# RC_CAR_Tx.net
KiCad netlist of a schematic drawn in EasyEDA
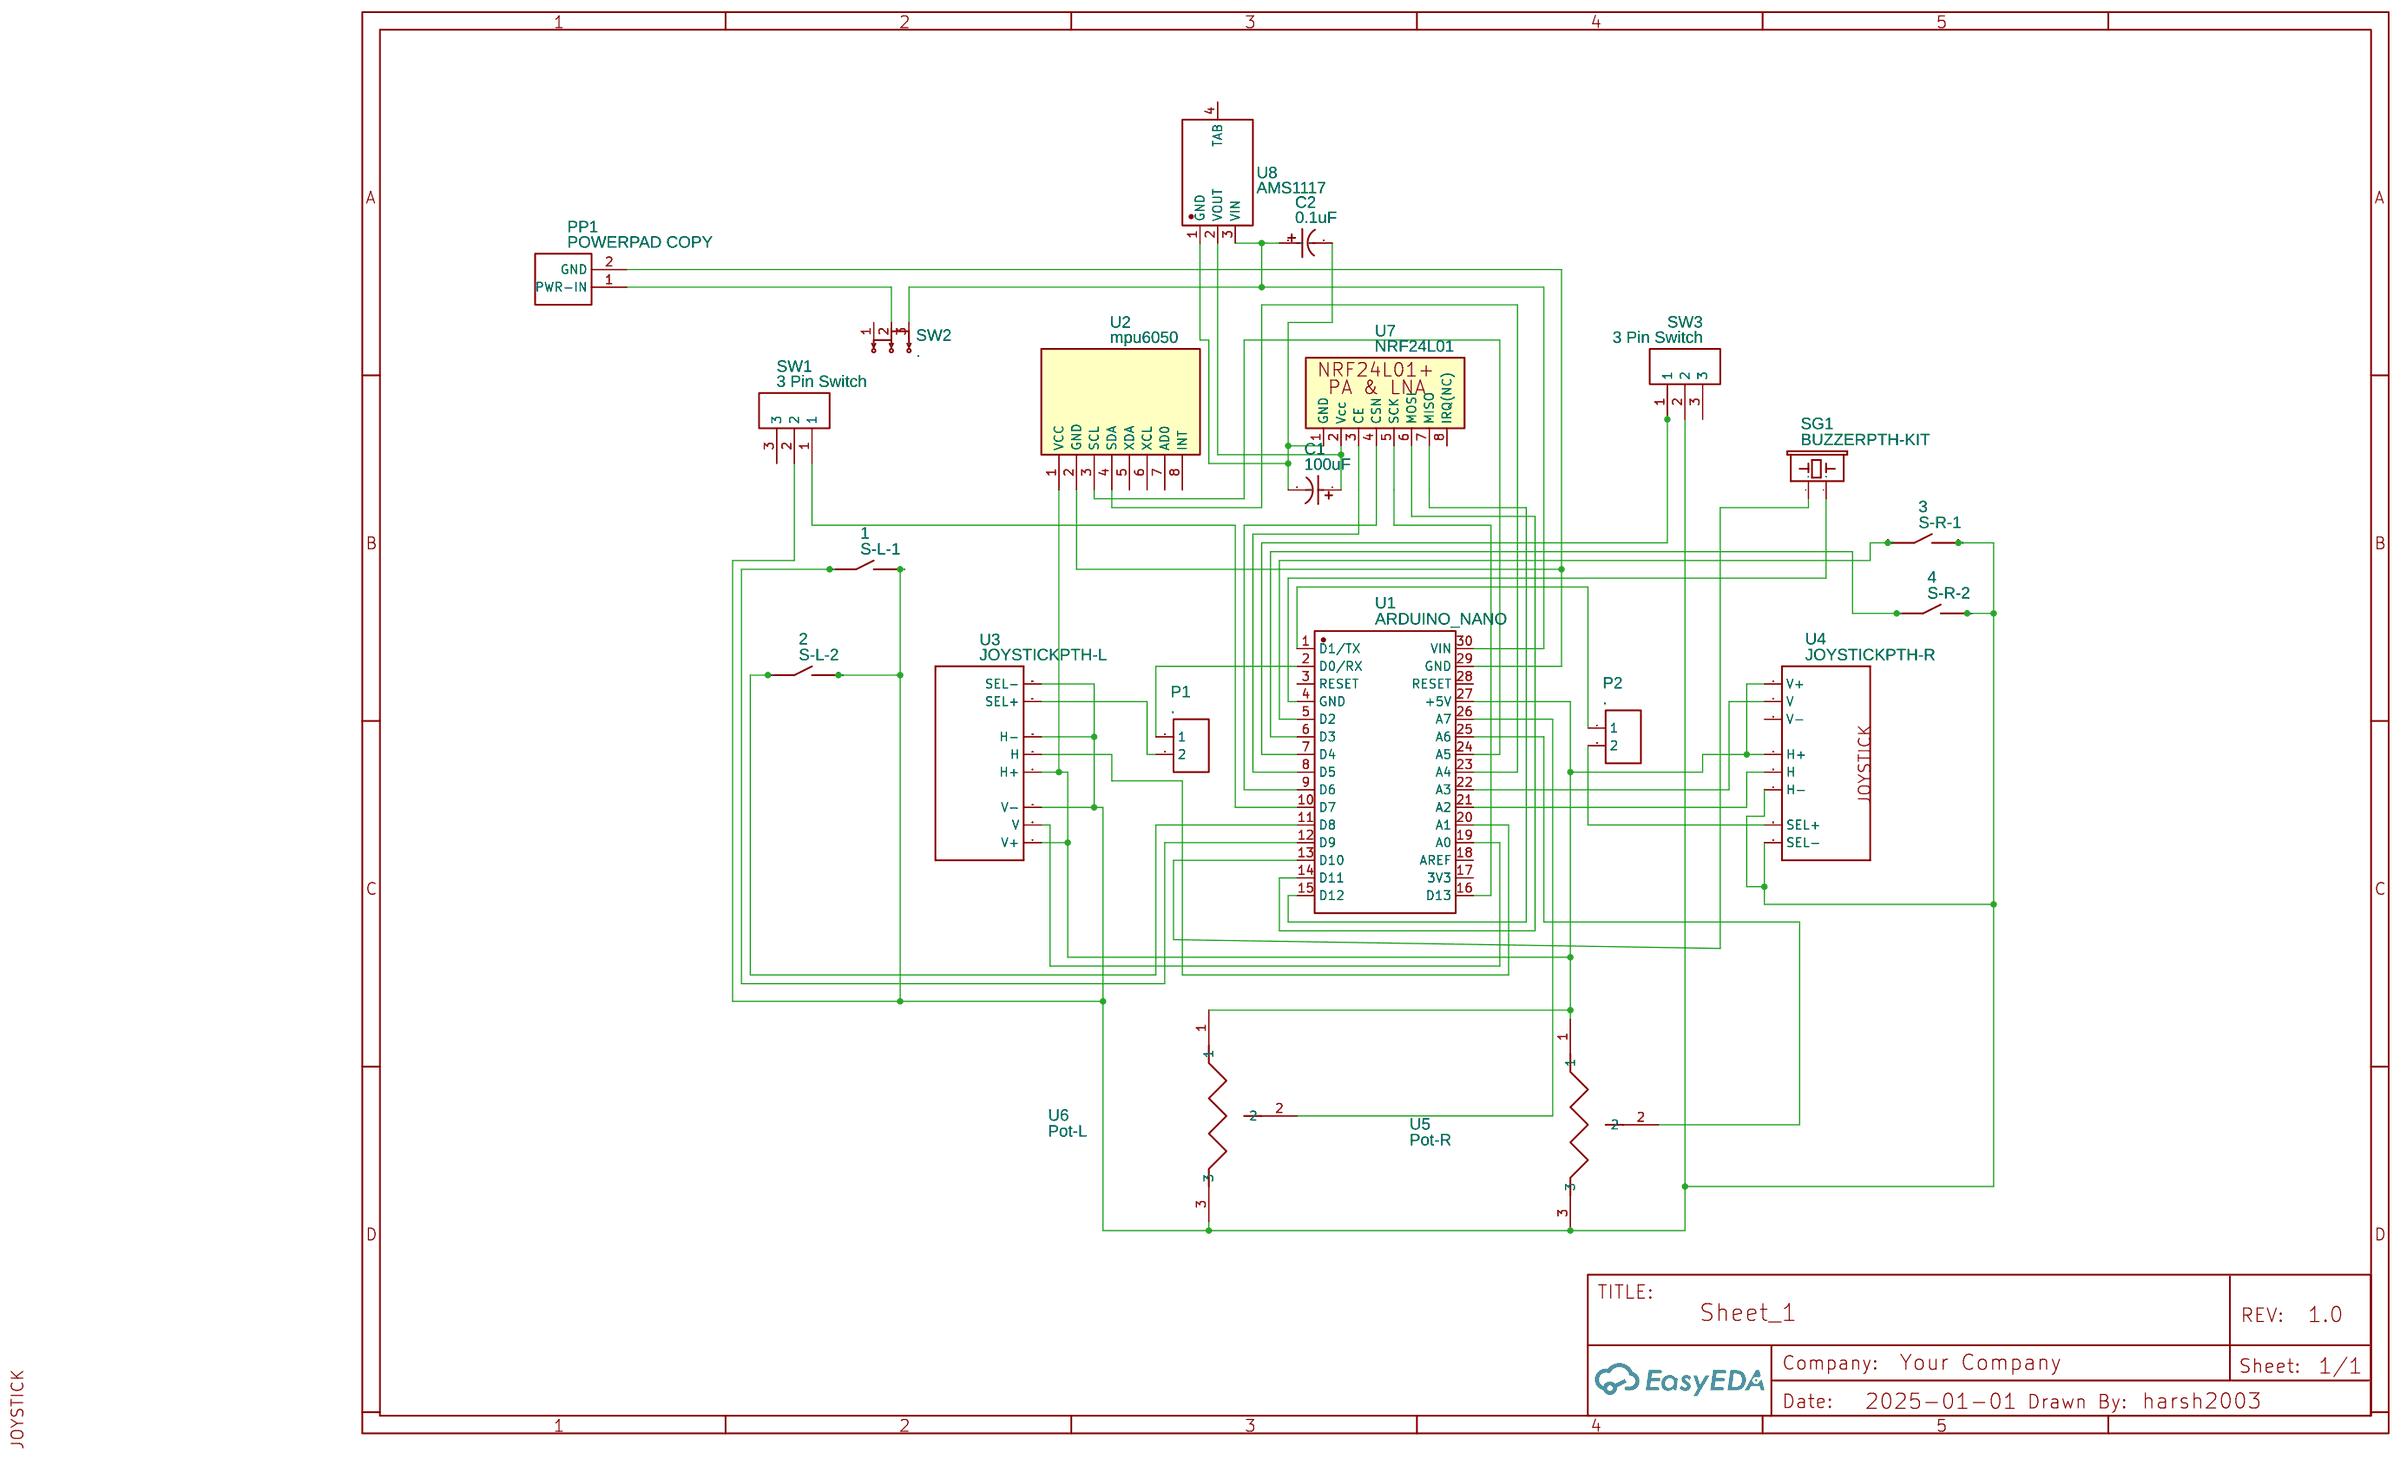
[diagram p0: schematic sheet]

(export (version "E")
  (design (tool "Eeschema 10.0.6"))
  (components
    (comp (ref "1") (value "S-L-1") (libsource (lib "") (part "4.5X4.5-SMD-TACTILE-SWITCH")))
    (comp (ref "2") (value "S-L-2") (libsource (lib "") (part "4.5X4.5-SMD-TACTILE-SWITCH")))
    (comp (ref "3") (value "S-R-1") (libsource (lib "") (part "4.5X4.5-SMD-TACTILE-SWITCH")))
    (comp (ref "4") (value "S-R-2") (libsource (lib "") (part "4.5X4.5-SMD-TACTILE-SWITCH")))
    (comp (ref "C1")
      (value "100uF")
      (fields (field (name "Manufacturer Part") "100uF 25V 6.3*11"))
      (libsource (lib "") (part "100uF 25V 6.3*11"))
    )
    (comp (ref "C2")
      (value "0.1uF")
      (fields (field (name "Manufacturer Part") "KF221M010E110A") (field (name "Manufacturer") "CapXon(丰宾)"))
      (libsource (lib "") (part "KF221M010E110A"))
    )
    (comp (ref "P1")
      (value ".")
      (fields (field (name "Manufacturer Part") "2.54-1*2P母") (field (name "Manufacturer") "BOOMELE(博穆精密)"))
      (libsource (lib "") (part "Header-Female-2.54_1x2"))
    )
    (comp (ref "P2")
      (value ".")
      (fields (field (name "Manufacturer Part") "2.54-1*2P母") (field (name "Manufacturer") "BOOMELE(博穆精密)"))
      (libsource (lib "") (part "Header-Female-2.54_1x2"))
    )
    (comp (ref "PP1") (value "POWERPAD COPY") (libsource (lib "") (part "POWERPAD COPY")))
    (comp (ref "SG1") (value "BUZZERPTH-KIT") (libsource (lib "") (part "BUZZERPTH-KIT")))
    (comp (ref "SW1")
      (value "3 Pin Switch")
      (fields
        (field (name "Manufacturer Part") "SS12D06")
        (field (name "Manufacturer") "Dongguan Kaifeng Electronic Technology Limited")
      )
      (libsource (lib "") (part "3 Pin Switch_1"))
    )
    (comp (ref "SW2")
      (value ".")
      (fields (field (name "Manufacturer Part") "SS-12F20-G070") (field (name "Manufacturer") "G-Switch(品赞)"))
      (libsource (lib "") (part "SS-12F20-G070"))
    )
    (comp (ref "SW3")
      (value "3 Pin Switch")
      (fields
        (field (name "Manufacturer Part") "SS12D06")
        (field (name "Manufacturer") "Dongguan Kaifeng Electronic Technology Limited")
      )
      (libsource (lib "") (part "3 Pin Switch"))
    )
    (comp (ref "U1") (value "ARDUINO_NANO") (libsource (lib "") (part "ARDUINO_NANO")))
    (comp (ref "U2") (value "mpu6050") (libsource (lib "") (part "mpu6050")))
    (comp (ref "U3") (value "JOYSTICKPTH-L") (libsource (lib "") (part "JOYSTICKPTH copy_1")))
    (comp (ref "U4") (value "JOYSTICKPTH-R") (libsource (lib "") (part "JOYSTICKPTH copy")))
    (comp (ref "U5") (value "Pot-R") (libsource (lib "") (part "100k potentiometer")))
    (comp (ref "U6") (value "Pot-L") (libsource (lib "") (part "100k potentiometer")))
    (comp (ref "U7")
      (value "NRF24L01")
      (fields (field (name "Manufacturer Part") "NRF24L01+") (field (name "Manufacturer") "Fo2sh"))
      (libsource (lib "") (part "AR_NRF24L01+PA+LNA"))
    )
    (comp (ref "U8")
      (value "AMS1117")
      (fields (field (name "Manufacturer Part") "AMS1117-1.8") (field (name "Manufacturer") "HGC(华冠)"))
      (libsource (lib "") (part "AMS1117-1.8_C498120"))
    )
  )
  (nets
    (net (code "1") (name "Net-(PP1-GND)") (class "Default")
      (node (ref "PP1") (pin "2") (pinfunction "GND_2") (pintype "unspecified"))
      (node (ref "U1") (pin "29") (pinfunction "GND_29") (pintype "unspecified"))
      (node (ref "U2") (pin "2") (pinfunction "GND_2") (pintype "unspecified"))
    )
    (net (code "2") (name "Net-(PP1-PWR-IN)") (class "Default")
      (node (ref "PP1") (pin "1") (pinfunction "PWR-IN_1") (pintype "unspecified"))
      (node (ref "SW2") (pin "2") (pinfunction "2_2") (pintype "unspecified"))
    )
    (net (code "3") (name "Net-(SG1-1)") (class "Default")
      (node (ref "SG1") (pin "+") (pinfunction "1_+") (pintype "unspecified"))
      (node (ref "U1") (pin "13") (pinfunction "D10_13") (pintype "unspecified"))
    )
    (net (code "4") (name "Net-(SG1-2)") (class "Default")
      (node (ref "SG1") (pin "-") (pinfunction "2_-") (pintype "unspecified"))
      (node (ref "U1") (pin "4") (pinfunction "GND_4") (pintype "unspecified"))
    )
    (net (code "5") (name "Net-(U1-+5V)") (class "Default")
      (node (ref "U1") (pin "27") (pinfunction "+5V_27") (pintype "unspecified"))
      (node (ref "U2") (pin "1") (pinfunction "VCC_1") (pintype "unspecified"))
      (node (ref "U3") (pin "H1") (pinfunction "H+_H1") (pintype "unspecified"))
      (node (ref "U3") (pin "V1") (pinfunction "V+_V1") (pintype "unspecified"))
      (node (ref "U4") (pin "H1") (pinfunction "H+_H1") (pintype "unspecified"))
      (node (ref "U4") (pin "V1") (pinfunction "V+_V1") (pintype "unspecified"))
      (node (ref "U5") (pin "1") (pinfunction "1_1") (pintype "unspecified"))
      (node (ref "U6") (pin "1") (pinfunction "1_1") (pintype "unspecified"))
    )
    (net (code "6") (name "Net-(U1-A0)") (class "Default")
      (node (ref "U1") (pin "19") (pinfunction "A0_19") (pintype "unspecified"))
      (node (ref "U3") (pin "V2") (pinfunction "V_V2") (pintype "unspecified"))
    )
    (net (code "7") (name "Net-(U1-A1)") (class "Default")
      (node (ref "U1") (pin "20") (pinfunction "A1_20") (pintype "unspecified"))
      (node (ref "U3") (pin "H2") (pinfunction "H_H2") (pintype "unspecified"))
    )
    (net (code "8") (name "Net-(U1-A2)") (class "Default")
      (node (ref "U1") (pin "21") (pinfunction "A2_21") (pintype "unspecified"))
      (node (ref "U4") (pin "H2") (pinfunction "H_H2") (pintype "unspecified"))
    )
    (net (code "9") (name "Net-(U1-A3)") (class "Default")
      (node (ref "U1") (pin "22") (pinfunction "A3_22") (pintype "unspecified"))
      (node (ref "U4") (pin "V2") (pinfunction "V_V2") (pintype "unspecified"))
    )
    (net (code "10") (name "Net-(U1-A4)") (class "Default")
      (node (ref "U1") (pin "23") (pinfunction "A4_23") (pintype "unspecified"))
      (node (ref "U2") (pin "4") (pinfunction "SDA_4") (pintype "unspecified"))
    )
    (net (code "11") (name "Net-(U1-A5)") (class "Default")
      (node (ref "U1") (pin "24") (pinfunction "A5_24") (pintype "unspecified"))
      (node (ref "U2") (pin "3") (pinfunction "SCL_3") (pintype "unspecified"))
    )
    (net (code "12") (name "Net-(U1-A6)") (class "Default")
      (node (ref "U1") (pin "25") (pinfunction "A6_25") (pintype "unspecified"))
      (node (ref "U5") (pin "2") (pinfunction "2_2") (pintype "unspecified"))
    )
    (net (code "13") (name "Net-(U1-A7)") (class "Default")
      (node (ref "U1") (pin "26") (pinfunction "A7_26") (pintype "unspecified"))
      (node (ref "U6") (pin "2") (pinfunction "2_2") (pintype "unspecified"))
    )
    (net (code "14") (name "Net-(U1-D0{slash}RX)") (class "Default")
      (node (ref "P1") (pin "1") (pinfunction "1_1") (pintype "input"))
      (node (ref "U1") (pin "2") (pinfunction "D0/RX_2") (pintype "unspecified"))
    )
    (net (code "15") (name "Net-(U1-D1{slash}TX)") (class "Default")
      (node (ref "P2") (pin "1") (pinfunction "1_1") (pintype "input"))
      (node (ref "U1") (pin "1") (pinfunction "D1/TX_1") (pintype "unspecified"))
    )
    (net (code "16") (name "Net-(U1-D2)") (class "Default")
      (node (ref "3") (pin "1.1") (pinfunction "S1_1.1") (pintype "bidirectional"))
      (node (ref "3") (pin "1.2") (pinfunction "S1_1.2") (pintype "bidirectional"))
      (node (ref "U1") (pin "5") (pinfunction "D2_5") (pintype "unspecified"))
    )
    (net (code "17") (name "Net-(U1-D3)") (class "Default")
      (node (ref "4") (pin "1.1") (pinfunction "S1_1.1") (pintype "bidirectional"))
      (node (ref "4") (pin "1.2") (pinfunction "S1_1.2") (pintype "bidirectional"))
      (node (ref "U1") (pin "6") (pinfunction "D3_6") (pintype "unspecified"))
    )
    (net (code "18") (name "Net-(U1-D4)") (class "Default")
      (node (ref "SW3") (pin "1") (pinfunction "1_1") (pintype "unspecified"))
      (node (ref "U1") (pin "7") (pinfunction "D4_7") (pintype "unspecified"))
    )
    (net (code "19") (name "Net-(U1-D5)") (class "Default")
      (node (ref "U1") (pin "8") (pinfunction "D5_8") (pintype "unspecified"))
      (node (ref "U7") (pin "3") (pinfunction "CE_3") (pintype "unspecified"))
    )
    (net (code "20") (name "Net-(U1-D6)") (class "Default")
      (node (ref "U1") (pin "9") (pinfunction "D6_9") (pintype "unspecified"))
      (node (ref "U7") (pin "4") (pinfunction "CSN_4") (pintype "unspecified"))
    )
    (net (code "21") (name "Net-(U1-D7)") (class "Default")
      (node (ref "SW1") (pin "1") (pinfunction "1_1") (pintype "unspecified"))
      (node (ref "U1") (pin "10") (pinfunction "D7_10") (pintype "unspecified"))
    )
    (net (code "22") (name "Net-(U1-D8)") (class "Default")
      (node (ref "2") (pin "1.1") (pinfunction "S1_1.1") (pintype "bidirectional"))
      (node (ref "2") (pin "1.2") (pinfunction "S1_1.2") (pintype "bidirectional"))
      (node (ref "U1") (pin "11") (pinfunction "D8_11") (pintype "unspecified"))
    )
    (net (code "23") (name "Net-(U1-D9)") (class "Default")
      (node (ref "1") (pin "1.1") (pinfunction "S1_1.1") (pintype "bidirectional"))
      (node (ref "1") (pin "1.2") (pinfunction "S1_1.2") (pintype "bidirectional"))
      (node (ref "U1") (pin "12") (pinfunction "D9_12") (pintype "unspecified"))
    )
    (net (code "24") (name "Net-(U1-D11)") (class "Default")
      (node (ref "U1") (pin "14") (pinfunction "D11_14") (pintype "unspecified"))
      (node (ref "U7") (pin "6") (pinfunction "MOSI_6") (pintype "unspecified"))
    )
    (net (code "25") (name "Net-(U1-D12)") (class "Default")
      (node (ref "U1") (pin "15") (pinfunction "D12_15") (pintype "unspecified"))
      (node (ref "U7") (pin "7") (pinfunction "MISO_7") (pintype "unspecified"))
    )
    (net (code "26") (name "Net-(U1-D13)") (class "Default")
      (node (ref "U1") (pin "16") (pinfunction "D13_16") (pintype "unspecified"))
      (node (ref "U7") (pin "5") (pinfunction "SCK_5") (pintype "unspecified"))
    )
    (net (code "27") (name "Net-(U1-VIN)") (class "Default")
      (node (ref "C2") (pin "1") (pinfunction "1_1") (pintype "input"))
      (node (ref "SW2") (pin "3") (pinfunction "3_3") (pintype "unspecified"))
      (node (ref "U1") (pin "30") (pinfunction "VIN_30") (pintype "unspecified"))
      (node (ref "U8") (pin "3") (pinfunction "VIN_3") (pintype "unspecified"))
    )
    (net (code "28") (name "Net-(U3-H-)") (class "Default")
      (node (ref "1") (pin "2.1") (pinfunction "S2_2.1") (pintype "bidirectional"))
      (node (ref "1") (pin "2.2") (pinfunction "S2_2.2") (pintype "bidirectional"))
      (node (ref "2") (pin "2.1") (pinfunction "S2_2.1") (pintype "bidirectional"))
      (node (ref "2") (pin "2.2") (pinfunction "S2_2.2") (pintype "bidirectional"))
      (node (ref "3") (pin "2.1") (pinfunction "S2_2.1") (pintype "bidirectional"))
      (node (ref "3") (pin "2.2") (pinfunction "S2_2.2") (pintype "bidirectional"))
      (node (ref "4") (pin "2.1") (pinfunction "S2_2.1") (pintype "bidirectional"))
      (node (ref "4") (pin "2.2") (pinfunction "S2_2.2") (pintype "bidirectional"))
      (node (ref "SW1") (pin "2") (pinfunction "2_2") (pintype "unspecified"))
      (node (ref "SW3") (pin "2") (pinfunction "2_2") (pintype "unspecified"))
      (node (ref "U3") (pin "B2A") (pinfunction "SEL-_B2A") (pintype "unspecified"))
      (node (ref "U3") (pin "H3") (pinfunction "H-_H3") (pintype "unspecified"))
      (node (ref "U3") (pin "V3") (pinfunction "V-_V3") (pintype "unspecified"))
      (node (ref "U4") (pin "B2A") (pinfunction "SEL-_B2A") (pintype "unspecified"))
      (node (ref "U4") (pin "H3") (pinfunction "H-_H3") (pintype "unspecified"))
      (node (ref "U5") (pin "3") (pinfunction "3_3") (pintype "unspecified"))
      (node (ref "U6") (pin "3") (pinfunction "3_3") (pintype "unspecified"))
    )
    (net (code "29") (name "Net-(U3-SEL+)") (class "Default")
      (node (ref "P1") (pin "2") (pinfunction "2_2") (pintype "input"))
      (node (ref "U3") (pin "B1A") (pinfunction "SEL+_B1A") (pintype "unspecified"))
    )
    (net (code "30") (name "Net-(U4-SEL+)") (class "Default")
      (node (ref "P2") (pin "2") (pinfunction "2_2") (pintype "input"))
      (node (ref "U4") (pin "B1A") (pinfunction "SEL+_B1A") (pintype "unspecified"))
    )
    (net (code "31") (name "Net-(U7-GND)") (class "Default")
      (node (ref "C1") (pin "2") (pinfunction "2_2") (pintype "input"))
      (node (ref "C2") (pin "2") (pinfunction "2_2") (pintype "input"))
      (node (ref "U7") (pin "1") (pinfunction "GND_1") (pintype "unspecified"))
      (node (ref "U8") (pin "1") (pinfunction "GND_1") (pintype "unspecified"))
    )
    (net (code "32") (name "Net-(U7-Vcc)") (class "Default")
      (node (ref "C1") (pin "1") (pinfunction "1_1") (pintype "input"))
      (node (ref "U7") (pin "2") (pinfunction "Vcc_2") (pintype "unspecified"))
      (node (ref "U8") (pin "2") (pinfunction "VOUT_2") (pintype "unspecified"))
    )
    (net (code "33") (name "unconnected-(SW1-Pad3)") (class "Default")
      (node (ref "SW1") (pin "3") (pinfunction "3_3") (pintype "unspecified"))
    )
    (net (code "34") (name "unconnected-(SW2-Pad1)") (class "Default")
      (node (ref "SW2") (pin "1") (pinfunction "1_1") (pintype "unspecified"))
    )
    (net (code "35") (name "unconnected-(SW3-Pad3)") (class "Default")
      (node (ref "SW3") (pin "3") (pinfunction "3_3") (pintype "unspecified"))
    )
    (net (code "36") (name "unconnected-(U1-3V3-Pad17)") (class "Default")
      (node (ref "U1") (pin "17") (pinfunction "3V3_17") (pintype "unspecified"))
    )
    (net (code "37") (name "unconnected-(U1-AREF-Pad18)") (class "Default")
      (node (ref "U1") (pin "18") (pinfunction "AREF_18") (pintype "unspecified"))
    )
    (net (code "38") (name "unconnected-(U1-RESET-Pad3)") (class "Default")
      (node (ref "U1") (pin "3") (pinfunction "RESET_3") (pintype "unspecified"))
    )
    (net (code "39") (name "unconnected-(U1-RESET-Pad28)") (class "Default")
      (node (ref "U1") (pin "28") (pinfunction "RESET_28") (pintype "unspecified"))
    )
    (net (code "40") (name "unconnected-(U2-AD0-Pad7)") (class "Default")
      (node (ref "U2") (pin "7") (pinfunction "AD0_7") (pintype "unspecified"))
    )
    (net (code "41") (name "unconnected-(U2-INT-Pad8)") (class "Default")
      (node (ref "U2") (pin "8") (pinfunction "INT_8") (pintype "unspecified"))
    )
    (net (code "42") (name "unconnected-(U2-XCL-Pad6)") (class "Default")
      (node (ref "U2") (pin "6") (pinfunction "XCL_6") (pintype "unspecified"))
    )
    (net (code "43") (name "unconnected-(U2-XDA-Pad5)") (class "Default")
      (node (ref "U2") (pin "5") (pinfunction "XDA_5") (pintype "unspecified"))
    )
    (net (code "44") (name "unconnected-(U4-V--PadV3)") (class "Default")
      (node (ref "U4") (pin "V3") (pinfunction "V-_V3") (pintype "unspecified"))
    )
    (net (code "45") (name "unconnected-(U7-IRQ(NC)-Pad8)") (class "Default")
      (node (ref "U7") (pin "8") (pinfunction "IRQ(NC)_8") (pintype "unspecified"))
    )
    (net (code "46") (name "unconnected-(U8-TAB-Pad4)") (class "Default")
      (node (ref "U8") (pin "4") (pinfunction "TAB_4") (pintype "unspecified"))
    )
  )
)
